# ROV_PCB.net
KiCad netlist of a schematic drawn in Altium Designer
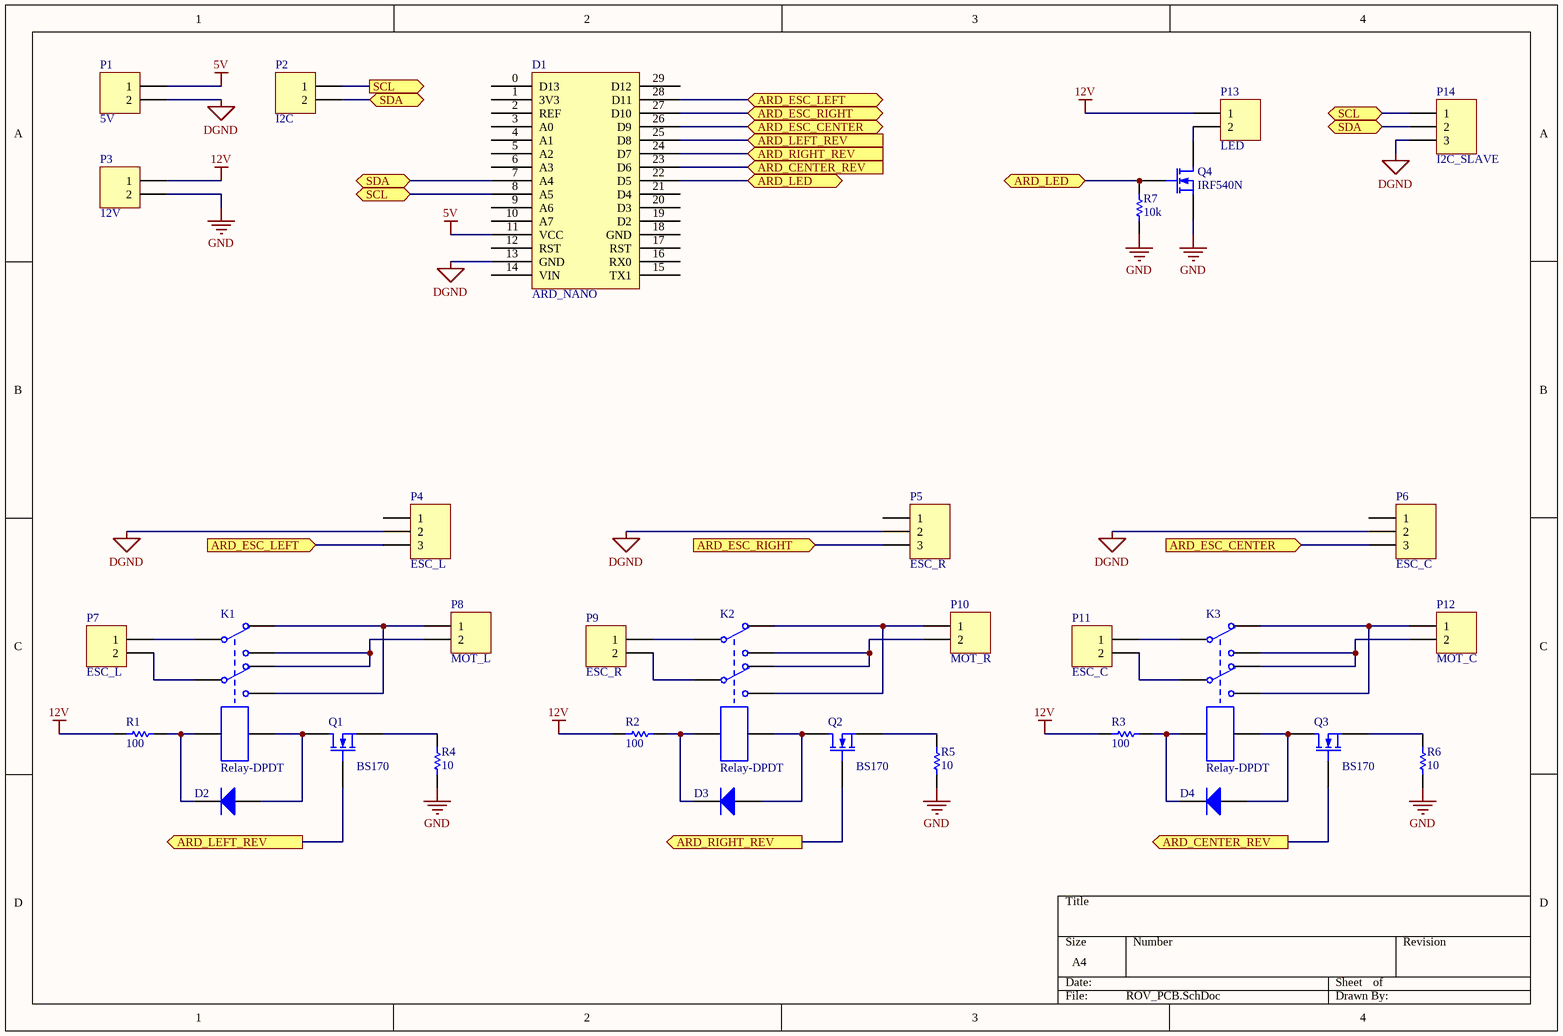
[diagram p0: ROV_PCB.SchDoc]

(export (version "E")
  (design (tool "Eeschema 10.0.6"))
  (components
    (comp (ref "D1") (value "ARD_NANO") (footprint "DIP30") (libsource (lib "Schlib1") (part "ARD_NANO")))
    (comp (ref "D2")
      (value "Diode 1N4001")
      (footprint "DO-41")
      (description "1 Amp General Purpose Rectifier")
      (fields (field (name "PUBLISHER") "Altium Limited"))
      (libsource (lib "Miscellaneous Devices") (part "Diode 1N4001"))
    )
    (comp (ref "D3")
      (value "Diode 1N4001")
      (footprint "DO-41")
      (description "1 Amp General Purpose Rectifier")
      (fields (field (name "PUBLISHER") "Altium Limited"))
      (libsource (lib "Miscellaneous Devices") (part "Diode 1N4001"))
    )
    (comp (ref "D4")
      (value "Diode 1N4001")
      (footprint "DO-41")
      (description "1 Amp General Purpose Rectifier")
      (fields (field (name "PUBLISHER") "Altium Limited"))
      (libsource (lib "Miscellaneous Devices") (part "Diode 1N4001"))
    )
    (comp (ref "K1")
      (value "Relay-DPDT")
      (footprint "RELAY_CUSTOM")
      (description "Dual-Pole Dual-Throw Relay")
      (fields (field (name "PUBLISHER") "Altium Limited"))
      (libsource (lib "Miscellaneous Devices") (part "Relay-DPDT"))
    )
    (comp (ref "K2")
      (value "Relay-DPDT")
      (footprint "RELAY_CUSTOM")
      (description "Dual-Pole Dual-Throw Relay")
      (fields (field (name "PUBLISHER") "Altium Limited"))
      (libsource (lib "Miscellaneous Devices") (part "Relay-DPDT"))
    )
    (comp (ref "K3")
      (value "Relay-DPDT")
      (footprint "RELAY_CUSTOM")
      (description "Dual-Pole Dual-Throw Relay")
      (fields (field (name "PUBLISHER") "Altium Limited"))
      (libsource (lib "Miscellaneous Devices") (part "Relay-DPDT"))
    )
    (comp (ref "P1")
      (value "5V")
      (footprint "KLEMA")
      (description "Header, 2-Pin")
      (fields (field (name "PUBLISHER") "Altium Limited"))
      (libsource (lib "") (part "Header 2_1"))
    )
    (comp (ref "P2")
      (value "I2C")
      (footprint "HDR1X2")
      (description "Header, 2-Pin")
      (fields (field (name "PUBLISHER") "Altium Limited"))
      (libsource (lib "") (part "Header 2_1"))
    )
    (comp (ref "P3")
      (value "12V")
      (footprint "KLEMA")
      (description "Header, 2-Pin")
      (fields (field (name "PUBLISHER") "Altium Limited"))
      (libsource (lib "") (part "Header 2_1"))
    )
    (comp (ref "P4")
      (value "ESC_L")
      (footprint "HDR1X3")
      (description "Header, 3-Pin")
      (fields (field (name "PUBLISHER") "Altium Limited"))
      (libsource (lib "Miscellaneous Connectors") (part "Header 3"))
    )
    (comp (ref "P5")
      (value "ESC_R")
      (footprint "HDR1X3")
      (description "Header, 3-Pin")
      (fields (field (name "PUBLISHER") "Altium Limited"))
      (libsource (lib "Miscellaneous Connectors") (part "Header 3"))
    )
    (comp (ref "P6")
      (value "ESC_C")
      (footprint "HDR1X3")
      (description "Header, 3-Pin")
      (fields (field (name "PUBLISHER") "Altium Limited"))
      (libsource (lib "Miscellaneous Connectors") (part "Header 3"))
    )
    (comp (ref "P7")
      (value "ESC_L")
      (footprint "KLEMA")
      (description "Header, 2-Pin")
      (fields (field (name "PUBLISHER") "Altium Limited"))
      (libsource (lib "") (part "Header 2_1"))
    )
    (comp (ref "P8")
      (value "MOT_L")
      (footprint "KLEMA")
      (description "Header, 2-Pin")
      (fields (field (name "PUBLISHER") "Altium Limited"))
      (libsource (lib "Miscellaneous Connectors") (part "Header 2"))
    )
    (comp (ref "P9")
      (value "ESC_R")
      (footprint "KLEMA")
      (description "Header, 2-Pin")
      (fields (field (name "PUBLISHER") "Altium Limited"))
      (libsource (lib "") (part "Header 2_1"))
    )
    (comp (ref "P10")
      (value "MOT_R")
      (footprint "KLEMA")
      (description "Header, 2-Pin")
      (fields (field (name "PUBLISHER") "Altium Limited"))
      (libsource (lib "Miscellaneous Connectors") (part "Header 2"))
    )
    (comp (ref "P11")
      (value "ESC_C")
      (footprint "KLEMA")
      (description "Header, 2-Pin")
      (fields (field (name "PUBLISHER") "Altium Limited"))
      (libsource (lib "") (part "Header 2_1"))
    )
    (comp (ref "P12")
      (value "MOT_C")
      (footprint "KLEMA")
      (description "Header, 2-Pin")
      (fields (field (name "PUBLISHER") "Altium Limited"))
      (libsource (lib "Miscellaneous Connectors") (part "Header 2"))
    )
    (comp (ref "P13")
      (value "LED")
      (footprint "KLEMA")
      (description "Header, 2-Pin")
      (fields (field (name "PUBLISHER") "Altium Limited"))
      (libsource (lib "Miscellaneous Connectors") (part "Header 2"))
    )
    (comp (ref "P14")
      (value "I2C_SLAVE")
      (footprint "HDR1X3")
      (description "Header, 3-Pin")
      (fields (field (name "PUBLISHER") "Altium Limited"))
      (libsource (lib "Miscellaneous Connectors") (part "Header 3"))
    )
    (comp (ref "Q1")
      (value "BS170")
      (footprint "HDR1X3")
      (description "N-Channel MOSFET")
      (fields (field (name "PUBLISHER") "Altium Limited"))
      (libsource (lib "Miscellaneous Devices") (part "MOSFET-N"))
    )
    (comp (ref "Q2")
      (value "BS170")
      (footprint "HDR1X3")
      (description "N-Channel MOSFET")
      (fields (field (name "PUBLISHER") "Altium Limited"))
      (libsource (lib "Miscellaneous Devices") (part "MOSFET-N"))
    )
    (comp (ref "Q3")
      (value "BS170")
      (footprint "HDR1X3")
      (description "N-Channel MOSFET")
      (fields (field (name "PUBLISHER") "Altium Limited"))
      (libsource (lib "Miscellaneous Devices") (part "MOSFET-N"))
    )
    (comp (ref "Q4")
      (value "IRF540N")
      (footprint "HDR1X3")
      (description "N-Channel MOSFET")
      (fields (field (name "PUBLISHER") "Altium Limited"))
      (libsource (lib "Miscellaneous Devices") (part "MOSFET-N"))
    )
    (comp (ref "R1")
      (value "100")
      (footprint "AXIAL-0.5")
      (description "Resistor")
      (fields (field (name "PUBLISHER") "Altium Limited"))
      (libsource (lib "Miscellaneous Devices") (part "Res1"))
    )
    (comp (ref "R2")
      (value "100")
      (footprint "AXIAL-0.5")
      (description "Resistor")
      (fields (field (name "PUBLISHER") "Altium Limited"))
      (libsource (lib "Miscellaneous Devices") (part "Res1"))
    )
    (comp (ref "R3")
      (value "100")
      (footprint "AXIAL-0.5")
      (description "Resistor")
      (fields (field (name "PUBLISHER") "Altium Limited"))
      (libsource (lib "Miscellaneous Devices") (part "Res1"))
    )
    (comp (ref "R4")
      (value "10")
      (footprint "AXIAL-0.5")
      (description "Resistor")
      (fields (field (name "PUBLISHER") "Altium Limited"))
      (libsource (lib "Miscellaneous Devices") (part "Res1"))
    )
    (comp (ref "R5")
      (value "10")
      (footprint "AXIAL-0.5")
      (description "Resistor")
      (fields (field (name "PUBLISHER") "Altium Limited"))
      (libsource (lib "Miscellaneous Devices") (part "Res1"))
    )
    (comp (ref "R6")
      (value "10")
      (footprint "AXIAL-0.5")
      (description "Resistor")
      (fields (field (name "PUBLISHER") "Altium Limited"))
      (libsource (lib "Miscellaneous Devices") (part "Res1"))
    )
    (comp (ref "R7")
      (value "10k")
      (footprint "AXIAL-0.4")
      (description "Resistor")
      (fields (field (name "PUBLISHER") "Altium Limited"))
      (libsource (lib "Miscellaneous Devices") (part "Res1"))
    )
  )
  (nets
    (net (code "1") (name "/ARD_CENTER_REV") (class "Default")
      (node (ref "D1") (pin "23") (pinfunction "D6_23") (pintype "passive"))
      (node (ref "Q3") (pin "2") (pinfunction "G_2") (pintype "passive"))
    )
    (net (code "2") (name "/ARD_ESC_CENTER") (class "Default")
      (node (ref "D1") (pin "26") (pinfunction "D9_26") (pintype "passive"))
      (node (ref "P6") (pin "3") (pinfunction "3_3") (pintype "passive"))
    )
    (net (code "3") (name "/ARD_ESC_LEFT") (class "Default")
      (node (ref "D1") (pin "28") (pinfunction "D11_28") (pintype "passive"))
      (node (ref "P4") (pin "3") (pinfunction "3_3") (pintype "passive"))
    )
    (net (code "4") (name "/ARD_ESC_RIGHT") (class "Default")
      (node (ref "D1") (pin "27") (pinfunction "D10_27") (pintype "passive"))
      (node (ref "P5") (pin "3") (pinfunction "3_3") (pintype "passive"))
    )
    (net (code "5") (name "/ARD_LED") (class "Default")
      (node (ref "D1") (pin "22") (pinfunction "D5_22") (pintype "passive"))
      (node (ref "Q4") (pin "2") (pinfunction "G_2") (pintype "passive"))
      (node (ref "R7") (pin "1") (pinfunction "1_1") (pintype "passive"))
    )
    (net (code "6") (name "/ARD_LEFT_REV") (class "Default")
      (node (ref "D1") (pin "25") (pinfunction "D8_25") (pintype "passive"))
      (node (ref "Q1") (pin "2") (pinfunction "G_2") (pintype "passive"))
    )
    (net (code "7") (name "/ARD_RIGHT_REV") (class "Default")
      (node (ref "D1") (pin "24") (pinfunction "D7_24") (pintype "passive"))
      (node (ref "Q2") (pin "2") (pinfunction "G_2") (pintype "passive"))
    )
    (net (code "8") (name "/SCL") (class "Default")
      (node (ref "D1") (pin "8") (pinfunction "A5_8") (pintype "passive"))
      (node (ref "P14") (pin "1") (pinfunction "1_1") (pintype "passive"))
      (node (ref "P2") (pin "1") (pinfunction "1_1") (pintype "passive"))
    )
    (net (code "9") (name "/SDA") (class "Default")
      (node (ref "D1") (pin "7") (pinfunction "A4_7") (pintype "passive"))
      (node (ref "P14") (pin "2") (pinfunction "2_2") (pintype "passive"))
      (node (ref "P2") (pin "2") (pinfunction "2_2") (pintype "passive"))
    )
    (net (code "10") (name "5V") (class "Default")
      (node (ref "D1") (pin "11") (pinfunction "VCC_11") (pintype "passive"))
      (node (ref "P1") (pin "1") (pinfunction "1_1") (pintype "passive"))
    )
    (net (code "11") (name "12V") (class "Default")
      (node (ref "P13") (pin "1") (pinfunction "1_1") (pintype "passive"))
      (node (ref "P3") (pin "1") (pinfunction "1_1") (pintype "passive"))
      (node (ref "R1") (pin "2") (pinfunction "2_2") (pintype "passive"))
      (node (ref "R2") (pin "2") (pinfunction "2_2") (pintype "passive"))
      (node (ref "R3") (pin "2") (pinfunction "2_2") (pintype "passive"))
    )
    (net (code "12") (name "DGND") (class "Default")
      (node (ref "D1") (pin "13") (pinfunction "GND_13") (pintype "passive"))
      (node (ref "P1") (pin "2") (pinfunction "2_2") (pintype "passive"))
      (node (ref "P14") (pin "3") (pinfunction "3_3") (pintype "passive"))
      (node (ref "P4") (pin "2") (pinfunction "2_2") (pintype "passive"))
      (node (ref "P5") (pin "2") (pinfunction "2_2") (pintype "passive"))
      (node (ref "P6") (pin "2") (pinfunction "2_2") (pintype "passive"))
    )
    (net (code "13") (name "GND") (class "Default")
      (node (ref "P3") (pin "2") (pinfunction "2_2") (pintype "passive"))
      (node (ref "Q4") (pin "3") (pinfunction "S_3") (pintype "passive"))
      (node (ref "R4") (pin "1") (pinfunction "1_1") (pintype "passive"))
      (node (ref "R5") (pin "1") (pinfunction "1_1") (pintype "passive"))
      (node (ref "R6") (pin "1") (pinfunction "1_1") (pintype "passive"))
      (node (ref "R7") (pin "2") (pinfunction "2_2") (pintype "passive"))
    )
    (net (code "14") (name "Net-(D2-A)") (class "Default")
      (node (ref "D2") (pin "1") (pinfunction "A_1") (pintype "passive"))
      (node (ref "K1") (pin "8") (pinfunction "8_8") (pintype "passive"))
      (node (ref "Q1") (pin "1") (pinfunction "D_1") (pintype "passive"))
    )
    (net (code "15") (name "Net-(D2-K)") (class "Default")
      (node (ref "D2") (pin "2") (pinfunction "K_2") (pintype "passive"))
      (node (ref "K1") (pin "7") (pinfunction "7_7") (pintype "passive"))
      (node (ref "R1") (pin "1") (pinfunction "1_1") (pintype "passive"))
    )
    (net (code "16") (name "Net-(D3-A)") (class "Default")
      (node (ref "D3") (pin "1") (pinfunction "A_1") (pintype "passive"))
      (node (ref "K2") (pin "8") (pinfunction "8_8") (pintype "passive"))
      (node (ref "Q2") (pin "1") (pinfunction "D_1") (pintype "passive"))
    )
    (net (code "17") (name "Net-(D3-K)") (class "Default")
      (node (ref "D3") (pin "2") (pinfunction "K_2") (pintype "passive"))
      (node (ref "K2") (pin "7") (pinfunction "7_7") (pintype "passive"))
      (node (ref "R2") (pin "1") (pinfunction "1_1") (pintype "passive"))
    )
    (net (code "18") (name "Net-(D4-A)") (class "Default")
      (node (ref "D4") (pin "1") (pinfunction "A_1") (pintype "passive"))
      (node (ref "K3") (pin "8") (pinfunction "8_8") (pintype "passive"))
      (node (ref "Q3") (pin "1") (pinfunction "D_1") (pintype "passive"))
    )
    (net (code "19") (name "Net-(D4-K)") (class "Default")
      (node (ref "D4") (pin "2") (pinfunction "K_2") (pintype "passive"))
      (node (ref "K3") (pin "7") (pinfunction "7_7") (pintype "passive"))
      (node (ref "R3") (pin "1") (pinfunction "1_1") (pintype "passive"))
    )
    (net (code "20") (name "Net-(K1-Pad1)") (class "Default")
      (node (ref "K1") (pin "1") (pinfunction "1_1") (pintype "passive"))
      (node (ref "P7") (pin "1") (pinfunction "1_1") (pintype "passive"))
    )
    (net (code "21") (name "Net-(K1-Pad2)") (class "Default")
      (node (ref "K1") (pin "2") (pinfunction "2_2") (pintype "passive"))
      (node (ref "K1") (pin "6") (pinfunction "6_6") (pintype "passive"))
      (node (ref "P8") (pin "1") (pinfunction "1_1") (pintype "passive"))
    )
    (net (code "22") (name "Net-(K1-Pad3)") (class "Default")
      (node (ref "K1") (pin "3") (pinfunction "3_3") (pintype "passive"))
      (node (ref "K1") (pin "5") (pinfunction "5_5") (pintype "passive"))
      (node (ref "P8") (pin "2") (pinfunction "2_2") (pintype "passive"))
    )
    (net (code "23") (name "Net-(K1-Pad4)") (class "Default")
      (node (ref "K1") (pin "4") (pinfunction "4_4") (pintype "passive"))
      (node (ref "P7") (pin "2") (pinfunction "2_2") (pintype "passive"))
    )
    (net (code "24") (name "Net-(K2-Pad1)") (class "Default")
      (node (ref "K2") (pin "1") (pinfunction "1_1") (pintype "passive"))
      (node (ref "P9") (pin "1") (pinfunction "1_1") (pintype "passive"))
    )
    (net (code "25") (name "Net-(K2-Pad2)") (class "Default")
      (node (ref "K2") (pin "2") (pinfunction "2_2") (pintype "passive"))
      (node (ref "K2") (pin "6") (pinfunction "6_6") (pintype "passive"))
      (node (ref "P10") (pin "1") (pinfunction "1_1") (pintype "passive"))
    )
    (net (code "26") (name "Net-(K2-Pad3)") (class "Default")
      (node (ref "K2") (pin "3") (pinfunction "3_3") (pintype "passive"))
      (node (ref "K2") (pin "5") (pinfunction "5_5") (pintype "passive"))
      (node (ref "P10") (pin "2") (pinfunction "2_2") (pintype "passive"))
    )
    (net (code "27") (name "Net-(K2-Pad4)") (class "Default")
      (node (ref "K2") (pin "4") (pinfunction "4_4") (pintype "passive"))
      (node (ref "P9") (pin "2") (pinfunction "2_2") (pintype "passive"))
    )
    (net (code "28") (name "Net-(K3-Pad1)") (class "Default")
      (node (ref "K3") (pin "1") (pinfunction "1_1") (pintype "passive"))
      (node (ref "P11") (pin "1") (pinfunction "1_1") (pintype "passive"))
    )
    (net (code "29") (name "Net-(K3-Pad2)") (class "Default")
      (node (ref "K3") (pin "2") (pinfunction "2_2") (pintype "passive"))
      (node (ref "K3") (pin "6") (pinfunction "6_6") (pintype "passive"))
      (node (ref "P12") (pin "1") (pinfunction "1_1") (pintype "passive"))
    )
    (net (code "30") (name "Net-(K3-Pad3)") (class "Default")
      (node (ref "K3") (pin "3") (pinfunction "3_3") (pintype "passive"))
      (node (ref "K3") (pin "5") (pinfunction "5_5") (pintype "passive"))
      (node (ref "P12") (pin "2") (pinfunction "2_2") (pintype "passive"))
    )
    (net (code "31") (name "Net-(K3-Pad4)") (class "Default")
      (node (ref "K3") (pin "4") (pinfunction "4_4") (pintype "passive"))
      (node (ref "P11") (pin "2") (pinfunction "2_2") (pintype "passive"))
    )
    (net (code "32") (name "Net-(Q1-S)") (class "Default")
      (node (ref "Q1") (pin "3") (pinfunction "S_3") (pintype "passive"))
      (node (ref "R4") (pin "2") (pinfunction "2_2") (pintype "passive"))
    )
    (net (code "33") (name "Net-(Q2-S)") (class "Default")
      (node (ref "Q2") (pin "3") (pinfunction "S_3") (pintype "passive"))
      (node (ref "R5") (pin "2") (pinfunction "2_2") (pintype "passive"))
    )
    (net (code "34") (name "Net-(Q3-S)") (class "Default")
      (node (ref "Q3") (pin "3") (pinfunction "S_3") (pintype "passive"))
      (node (ref "R6") (pin "2") (pinfunction "2_2") (pintype "passive"))
    )
    (net (code "35") (name "Net-(Q4-D)") (class "Default")
      (node (ref "P13") (pin "2") (pinfunction "2_2") (pintype "passive"))
      (node (ref "Q4") (pin "1") (pinfunction "D_1") (pintype "passive"))
    )
    (net (code "36") (name "unconnected-(D1-3V3-Pad1)") (class "Default")
      (node (ref "D1") (pin "1") (pinfunction "3V3_1") (pintype "passive"))
    )
    (net (code "37") (name "unconnected-(D1-A0-Pad3)") (class "Default")
      (node (ref "D1") (pin "3") (pinfunction "A0_3") (pintype "passive"))
    )
    (net (code "38") (name "unconnected-(D1-A1-Pad4)") (class "Default")
      (node (ref "D1") (pin "4") (pinfunction "A1_4") (pintype "passive"))
    )
    (net (code "39") (name "unconnected-(D1-A2-Pad5)") (class "Default")
      (node (ref "D1") (pin "5") (pinfunction "A2_5") (pintype "passive"))
    )
    (net (code "40") (name "unconnected-(D1-A3-Pad6)") (class "Default")
      (node (ref "D1") (pin "6") (pinfunction "A3_6") (pintype "passive"))
    )
    (net (code "41") (name "unconnected-(D1-A6-Pad9)") (class "Default")
      (node (ref "D1") (pin "9") (pinfunction "A6_9") (pintype "passive"))
    )
    (net (code "42") (name "unconnected-(D1-A7-Pad10)") (class "Default")
      (node (ref "D1") (pin "10") (pinfunction "A7_10") (pintype "passive"))
    )
    (net (code "43") (name "unconnected-(D1-D2-Pad19)") (class "Default")
      (node (ref "D1") (pin "19") (pinfunction "D2_19") (pintype "passive"))
    )
    (net (code "44") (name "unconnected-(D1-D3-Pad20)") (class "Default")
      (node (ref "D1") (pin "20") (pinfunction "D3_20") (pintype "passive"))
    )
    (net (code "45") (name "unconnected-(D1-D4-Pad21)") (class "Default")
      (node (ref "D1") (pin "21") (pinfunction "D4_21") (pintype "passive"))
    )
    (net (code "46") (name "unconnected-(D1-D12-Pad29)") (class "Default")
      (node (ref "D1") (pin "29") (pinfunction "D12_29") (pintype "passive"))
    )
    (net (code "47") (name "unconnected-(D1-D13-Pad0)") (class "Default")
      (node (ref "D1") (pin "0") (pinfunction "D13_0") (pintype "passive"))
    )
    (net (code "48") (name "unconnected-(D1-GND-Pad18)") (class "Default")
      (node (ref "D1") (pin "18") (pinfunction "GND_18") (pintype "passive"))
    )
    (net (code "49") (name "unconnected-(D1-REF-Pad2)") (class "Default")
      (node (ref "D1") (pin "2") (pinfunction "REF_2") (pintype "passive"))
    )
    (net (code "50") (name "unconnected-(D1-RST-Pad12)") (class "Default")
      (node (ref "D1") (pin "12") (pinfunction "RST_12") (pintype "passive"))
    )
    (net (code "51") (name "unconnected-(D1-RST-Pad17)") (class "Default")
      (node (ref "D1") (pin "17") (pinfunction "RST_17") (pintype "passive"))
    )
    (net (code "52") (name "unconnected-(D1-RX0-Pad16)") (class "Default")
      (node (ref "D1") (pin "16") (pinfunction "RX0_16") (pintype "passive"))
    )
    (net (code "53") (name "unconnected-(D1-TX1-Pad15)") (class "Default")
      (node (ref "D1") (pin "15") (pinfunction "TX1_15") (pintype "passive"))
    )
    (net (code "54") (name "unconnected-(D1-VIN-Pad14)") (class "Default")
      (node (ref "D1") (pin "14") (pinfunction "VIN_14") (pintype "passive"))
    )
    (net (code "55") (name "unconnected-(P4-Pad1)") (class "Default")
      (node (ref "P4") (pin "1") (pinfunction "1_1") (pintype "passive"))
    )
    (net (code "56") (name "unconnected-(P5-Pad1)") (class "Default")
      (node (ref "P5") (pin "1") (pinfunction "1_1") (pintype "passive"))
    )
    (net (code "57") (name "unconnected-(P6-Pad1)") (class "Default")
      (node (ref "P6") (pin "1") (pinfunction "1_1") (pintype "passive"))
    )
  )
)
